# drive_board.net
KiCad netlist of a schematic drawn in EAGLE
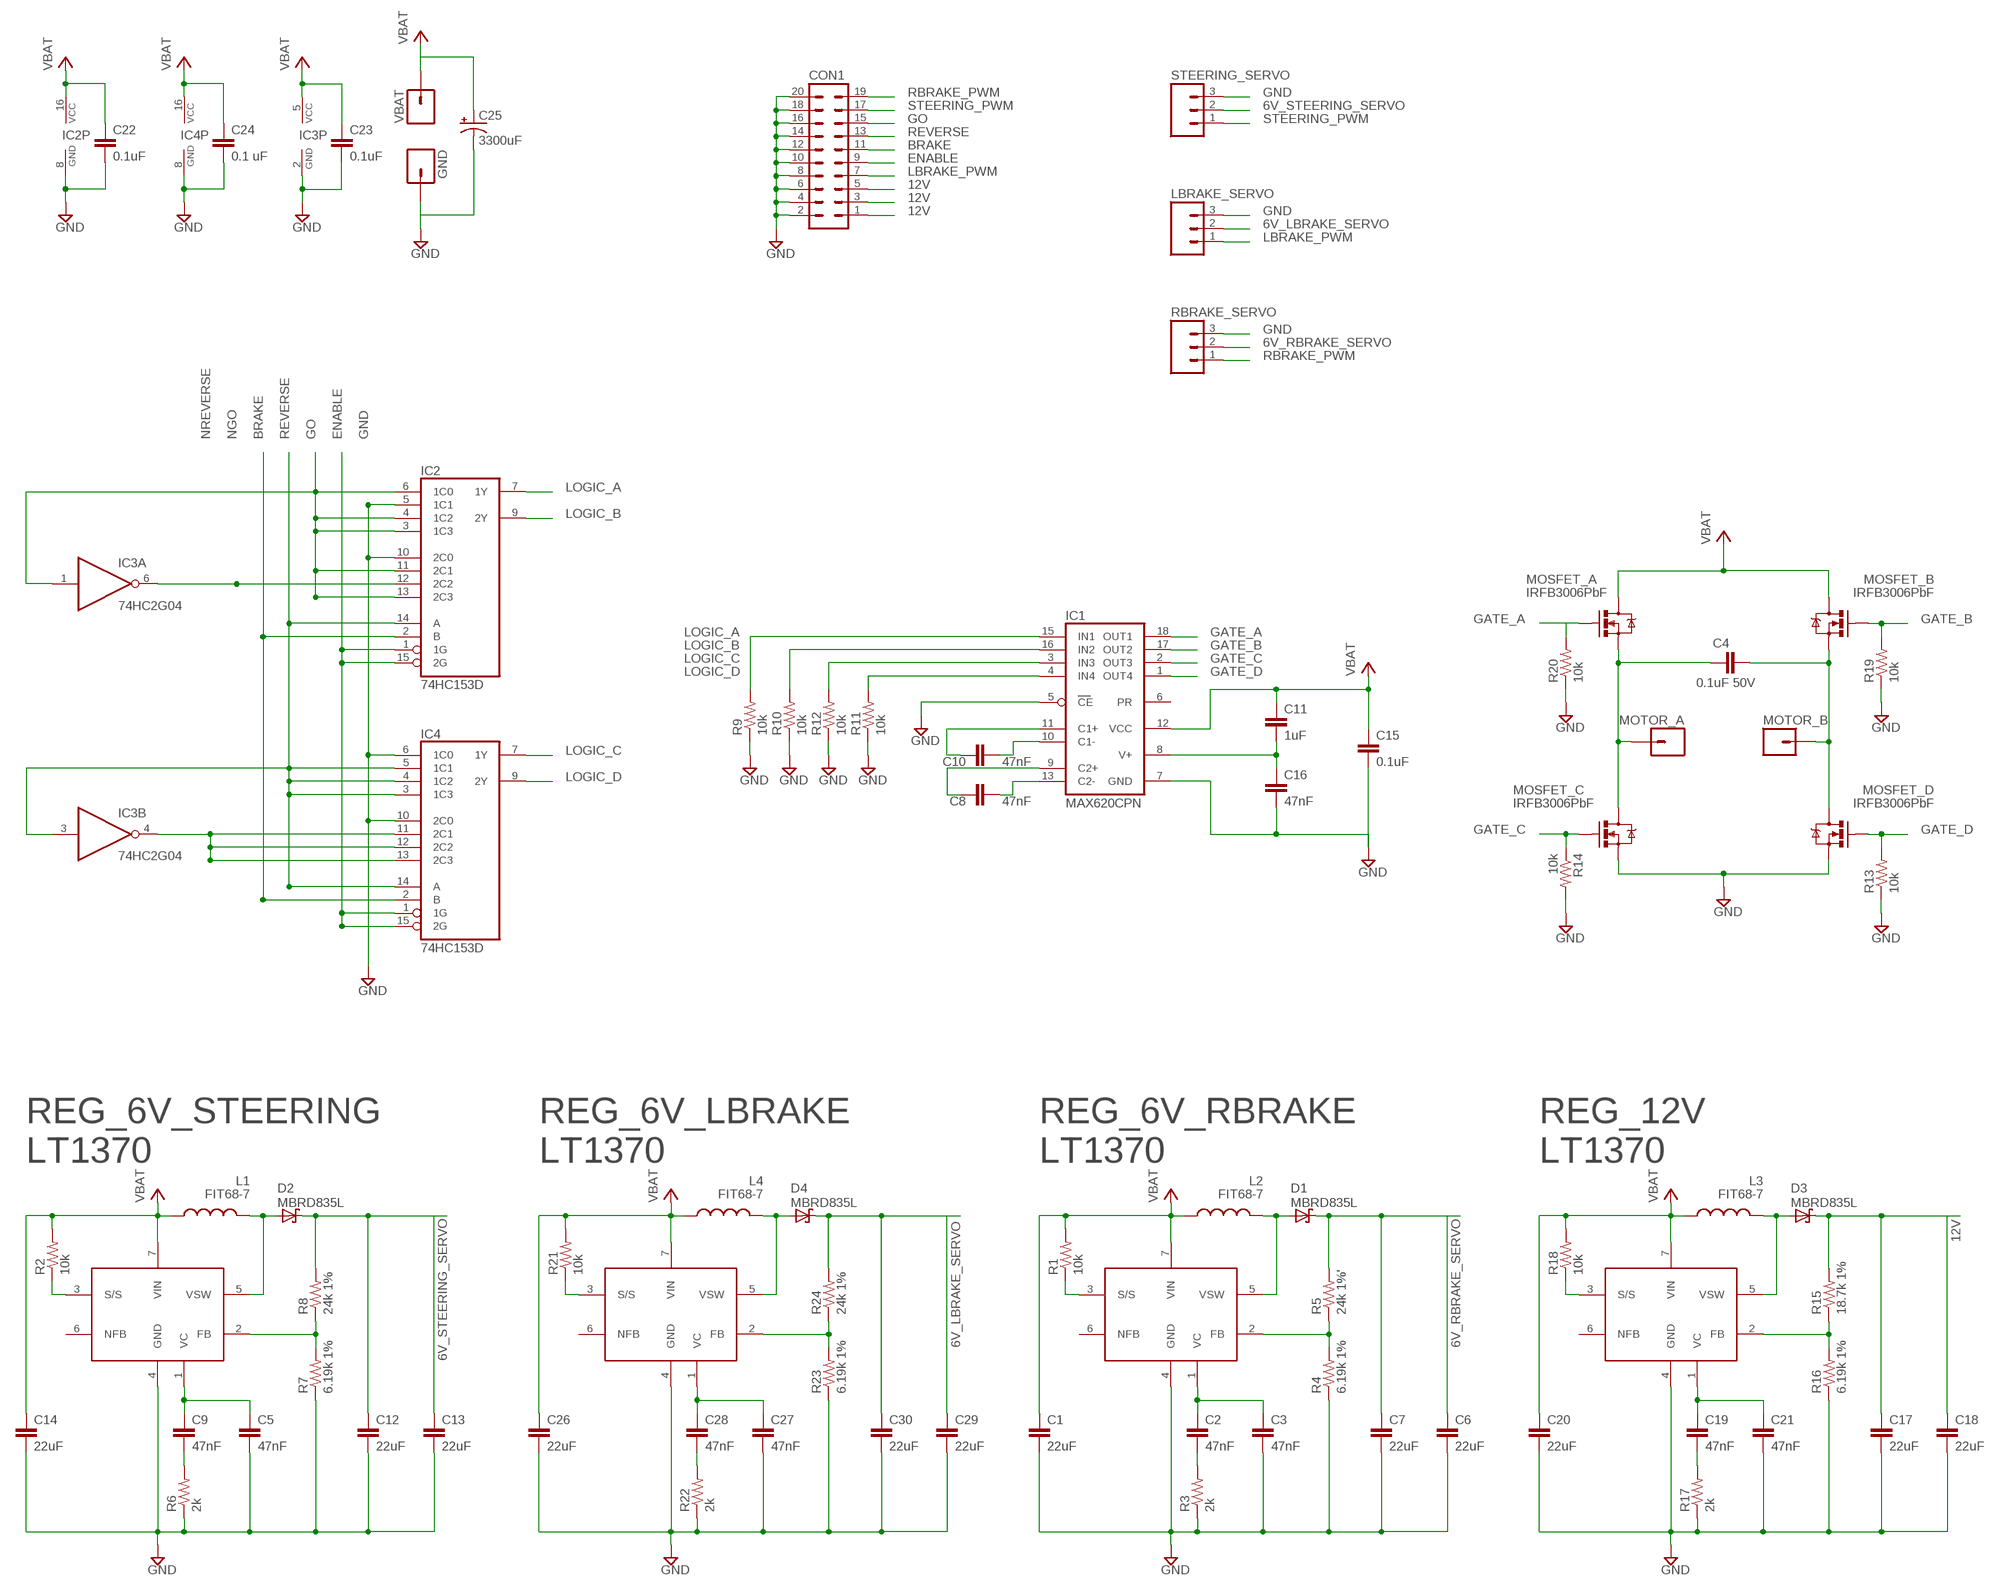
[diagram p0: schematic, sheet 1]

(export (version "E")
  (design (tool "Eeschema 10.0.6"))
  (components
    (comp (ref "C1")
      (value "22uF")
      (footprint "eagle-import:CAPACITOR_CASE_D")
      (libsource (lib "eagle-import") (part "TPSD226M025R0200"))
    )
    (comp (ref "C2")
      (value "47nF")
      (footprint "eagle-import:0603-CAP")
      (libsource (lib "eagle-import") (part "CAP0603-CAP"))
    )
    (comp (ref "C3")
      (value "47nF")
      (footprint "eagle-import:0603-CAP")
      (libsource (lib "eagle-import") (part "CAP0603-CAP"))
    )
    (comp (ref "C4")
      (value "0.1uF 50V")
      (footprint "eagle-import:0603-CAP")
      (libsource (lib "eagle-import") (part "CAP0603-CAP"))
    )
    (comp (ref "C5")
      (value "47nF")
      (footprint "eagle-import:0603-CAP")
      (libsource (lib "eagle-import") (part "CAP0603-CAP"))
    )
    (comp (ref "C6")
      (value "22uF")
      (footprint "eagle-import:CAPACITOR_CASE_D")
      (libsource (lib "eagle-import") (part "TPSD226M025R0200"))
    )
    (comp (ref "C7")
      (value "22uF")
      (footprint "eagle-import:CAPACITOR_CASE_D")
      (libsource (lib "eagle-import") (part "TPSD226M025R0200"))
    )
    (comp (ref "C8")
      (value "47nF")
      (footprint "eagle-import:0603-CAP")
      (libsource (lib "eagle-import") (part "CAP0603-CAP"))
    )
    (comp (ref "C9")
      (value "47nF")
      (footprint "eagle-import:0603-CAP")
      (libsource (lib "eagle-import") (part "CAP0603-CAP"))
    )
    (comp (ref "C10")
      (value "47nF")
      (footprint "eagle-import:0603-CAP")
      (libsource (lib "eagle-import") (part "CAP0603-CAP"))
    )
    (comp (ref "C11")
      (value "1uF")
      (footprint "eagle-import:0603-CAP")
      (libsource (lib "eagle-import") (part "CAP0603-CAP"))
    )
    (comp (ref "C12")
      (value "22uF")
      (footprint "eagle-import:CAPACITOR_CASE_D")
      (libsource (lib "eagle-import") (part "TPSD226M025R0200"))
    )
    (comp (ref "C13")
      (value "22uF")
      (footprint "eagle-import:CAPACITOR_CASE_D")
      (libsource (lib "eagle-import") (part "TPSD226M025R0200"))
    )
    (comp (ref "C14")
      (value "22uF")
      (footprint "eagle-import:CAPACITOR_CASE_D")
      (libsource (lib "eagle-import") (part "TPSD226M025R0200"))
    )
    (comp (ref "C15")
      (value "0.1uF")
      (footprint "eagle-import:0603-CAP")
      (libsource (lib "eagle-import") (part "CAP0603-CAP"))
    )
    (comp (ref "C16")
      (value "47nF")
      (footprint "eagle-import:0603-CAP")
      (libsource (lib "eagle-import") (part "CAP0603-CAP"))
    )
    (comp (ref "C17")
      (value "22uF")
      (footprint "eagle-import:CAPACITOR_CASE_D")
      (libsource (lib "eagle-import") (part "TPSD226M025R0200"))
    )
    (comp (ref "C18")
      (value "22uF")
      (footprint "eagle-import:CAPACITOR_CASE_D")
      (libsource (lib "eagle-import") (part "TPSD226M025R0200"))
    )
    (comp (ref "C19")
      (value "47nF")
      (footprint "eagle-import:0603-CAP")
      (libsource (lib "eagle-import") (part "CAP0603-CAP"))
    )
    (comp (ref "C20")
      (value "22uF")
      (footprint "eagle-import:CAPACITOR_CASE_D")
      (libsource (lib "eagle-import") (part "TPSD226M025R0200"))
    )
    (comp (ref "C21")
      (value "47nF")
      (footprint "eagle-import:0603-CAP")
      (libsource (lib "eagle-import") (part "CAP0603-CAP"))
    )
    (comp (ref "C22")
      (value "0.1uF")
      (footprint "eagle-import:0603-CAP")
      (libsource (lib "eagle-import") (part "SparkFun-Passives_CAP0603-CAP"))
    )
    (comp (ref "C23")
      (value "0.1uF")
      (footprint "eagle-import:0603-CAP")
      (libsource (lib "eagle-import") (part "SparkFun-Passives_CAP0603-CAP"))
    )
    (comp (ref "C24")
      (value "0.1 uF")
      (footprint "eagle-import:0603-CAP")
      (libsource (lib "eagle-import") (part "SparkFun-Passives_CAP0603-CAP"))
    )
    (comp (ref "C25")
      (value "3300uF")
      (footprint "eagle-import:CPOL-RADIAL-100UF-25V")
      (libsource (lib "eagle-import") (part "CAP_POLPTH1"))
    )
    (comp (ref "C26")
      (value "22uF")
      (footprint "eagle-import:CAPACITOR_CASE_D")
      (libsource (lib "eagle-import") (part "TPSD226M025R0200"))
    )
    (comp (ref "C27")
      (value "47nF")
      (footprint "eagle-import:0603-CAP")
      (libsource (lib "eagle-import") (part "CAP0603-CAP"))
    )
    (comp (ref "C28")
      (value "47nF")
      (footprint "eagle-import:0603-CAP")
      (libsource (lib "eagle-import") (part "CAP0603-CAP"))
    )
    (comp (ref "C29")
      (value "22uF")
      (footprint "eagle-import:CAPACITOR_CASE_D")
      (libsource (lib "eagle-import") (part "TPSD226M025R0200"))
    )
    (comp (ref "C30")
      (value "22uF")
      (footprint "eagle-import:CAPACITOR_CASE_D")
      (libsource (lib "eagle-import") (part "TPSD226M025R0200"))
    )
    (comp (ref "CON1")
      (value "ML20")
      (footprint "eagle-import:ML20")
      (libsource (lib "eagle-import") (part "ML20"))
    )
    (comp (ref "D1")
      (value "MBRD835L")
      (footprint "eagle-import:DPACK_1")
      (libsource (lib "eagle-import") (part "MBRD835L"))
    )
    (comp (ref "D2")
      (value "MBRD835L")
      (footprint "eagle-import:DPACK_1")
      (libsource (lib "eagle-import") (part "MBRD835L"))
    )
    (comp (ref "D3")
      (value "MBRD835L")
      (footprint "eagle-import:DPACK_1")
      (libsource (lib "eagle-import") (part "MBRD835L"))
    )
    (comp (ref "D4")
      (value "MBRD835L")
      (footprint "eagle-import:DPACK_1")
      (libsource (lib "eagle-import") (part "MBRD835L"))
    )
    (comp (ref "GND")
      (value "GND")
      (footprint "eagle-import:PAD_12GA")
      (libsource (lib "eagle-import") (part "PAD_12GAPTH"))
    )
    (comp (ref "IC1")
      (value "MAX620CPN")
      (footprint "eagle-import:DIL18")
      (fields (field (name "MPN") "MAX620CPN+"))
      (libsource (lib "eagle-import") (part "MAX620CPN"))
    )
    (comp (ref "IC2")
      (value "74HC153D")
      (footprint "eagle-import:SO16")
      (libsource (lib "eagle-import") (part "74153DHC"))
    )
    (comp (ref "IC3")
      (value "74HC2G04")
      (footprint "eagle-import:TSSOP6")
      (libsource (lib "eagle-import") (part "74HC2G04"))
    )
    (comp (ref "IC4")
      (value "74HC153D")
      (footprint "eagle-import:SO16")
      (libsource (lib "eagle-import") (part "74153DHC"))
    )
    (comp (ref "L1")
      (value "FIT68-7")
      (footprint "eagle-import:TOROID_INDUCTOR")
      (libsource (lib "eagle-import") (part "INDUCTOR"))
    )
    (comp (ref "L2")
      (value "FIT68-7")
      (footprint "eagle-import:TOROID_INDUCTOR")
      (libsource (lib "eagle-import") (part "INDUCTOR"))
    )
    (comp (ref "L3")
      (value "FIT68-7")
      (footprint "eagle-import:TOROID_INDUCTOR")
      (libsource (lib "eagle-import") (part "INDUCTOR"))
    )
    (comp (ref "L4")
      (value "FIT68-7")
      (footprint "eagle-import:TOROID_INDUCTOR")
      (libsource (lib "eagle-import") (part "INDUCTOR"))
    )
    (comp (ref "LBRAKE_SERVO")
      (value "M03POLAR")
      (footprint "eagle-import:MOLEX-1X3")
      (libsource (lib "eagle-import") (part "M03POLAR"))
    )
    (comp (ref "MOSFET_A")
      (value "IRFB3006PbF")
      (footprint "eagle-import:TO220V")
      (libsource (lib "eagle-import") (part "MOSFET-NCHANNELPTH2"))
    )
    (comp (ref "MOSFET_B")
      (value "IRFB3006PbF")
      (footprint "eagle-import:TO220V")
      (libsource (lib "eagle-import") (part "MOSFET-NCHANNELPTH2"))
    )
    (comp (ref "MOSFET_C")
      (value "IRFB3006PbF")
      (footprint "eagle-import:TO220V")
      (libsource (lib "eagle-import") (part "MOSFET-NCHANNELPTH2"))
    )
    (comp (ref "MOSFET_D")
      (value "IRFB3006PbF")
      (footprint "eagle-import:TO220V")
      (libsource (lib "eagle-import") (part "MOSFET-NCHANNELPTH2"))
    )
    (comp (ref "MOTOR_A")
      (value "MOTOR A")
      (footprint "eagle-import:PAD_12GA")
      (libsource (lib "eagle-import") (part "PAD_12GAPTH"))
    )
    (comp (ref "MOTOR_B")
      (value "MOTOR B")
      (footprint "eagle-import:PAD_12GA")
      (libsource (lib "eagle-import") (part "PAD_12GAPTH"))
    )
    (comp (ref "R1")
      (value "10k")
      (footprint "eagle-import:0603-RES")
      (libsource (lib "eagle-import") (part "RESISTOR0603-RES"))
    )
    (comp (ref "R2")
      (value "10k")
      (footprint "eagle-import:0603-RES")
      (libsource (lib "eagle-import") (part "RESISTOR0603-RES"))
    )
    (comp (ref "R3")
      (value "2k")
      (footprint "eagle-import:0603-RES")
      (libsource (lib "eagle-import") (part "RESISTOR0603-RES"))
    )
    (comp (ref "R4")
      (value "6.19k 1%")
      (footprint "eagle-import:0603-RES")
      (libsource (lib "eagle-import") (part "RESISTOR0603-RES"))
    )
    (comp (ref "R5")
      (value "24k 1%'")
      (footprint "eagle-import:0603-RES")
      (libsource (lib "eagle-import") (part "RESISTOR0603-RES"))
    )
    (comp (ref "R6")
      (value "2k")
      (footprint "eagle-import:0603-RES")
      (libsource (lib "eagle-import") (part "RESISTOR0603-RES"))
    )
    (comp (ref "R7")
      (value "6.19k 1%")
      (footprint "eagle-import:0603-RES")
      (libsource (lib "eagle-import") (part "RESISTOR0603-RES"))
    )
    (comp (ref "R8")
      (value "24k 1%")
      (footprint "eagle-import:0603-RES")
      (libsource (lib "eagle-import") (part "RESISTOR0603-RES"))
    )
    (comp (ref "R9")
      (value "10k")
      (footprint "eagle-import:0603-RES")
      (libsource (lib "eagle-import") (part "RESISTOR0603-RES"))
    )
    (comp (ref "R10")
      (value "10k")
      (footprint "eagle-import:0603-RES")
      (libsource (lib "eagle-import") (part "RESISTOR0603-RES"))
    )
    (comp (ref "R11")
      (value "10k")
      (footprint "eagle-import:0603-RES")
      (libsource (lib "eagle-import") (part "RESISTOR0603-RES"))
    )
    (comp (ref "R12")
      (value "10k")
      (footprint "eagle-import:0603-RES")
      (libsource (lib "eagle-import") (part "RESISTOR0603-RES"))
    )
    (comp (ref "R13")
      (value "10k")
      (footprint "eagle-import:0603-RES")
      (libsource (lib "eagle-import") (part "RESISTOR0603-RES"))
    )
    (comp (ref "R14")
      (value "10k")
      (footprint "eagle-import:0603-RES")
      (libsource (lib "eagle-import") (part "RESISTOR0603-RES"))
    )
    (comp (ref "R15")
      (value "18.7k 1%")
      (footprint "eagle-import:0603-RES")
      (libsource (lib "eagle-import") (part "RESISTOR0603-RES"))
    )
    (comp (ref "R16")
      (value "6.19k 1%")
      (footprint "eagle-import:0603-RES")
      (libsource (lib "eagle-import") (part "RESISTOR0603-RES"))
    )
    (comp (ref "R17")
      (value "2k")
      (footprint "eagle-import:0603-RES")
      (libsource (lib "eagle-import") (part "RESISTOR0603-RES"))
    )
    (comp (ref "R18")
      (value "10k")
      (footprint "eagle-import:0603-RES")
      (libsource (lib "eagle-import") (part "RESISTOR0603-RES"))
    )
    (comp (ref "R19")
      (value "10k")
      (footprint "eagle-import:0603-RES")
      (libsource (lib "eagle-import") (part "RESISTOR0603-RES"))
    )
    (comp (ref "R20")
      (value "10k")
      (footprint "eagle-import:0603-RES")
      (libsource (lib "eagle-import") (part "RESISTOR0603-RES"))
    )
    (comp (ref "R21")
      (value "10k")
      (footprint "eagle-import:0603-RES")
      (libsource (lib "eagle-import") (part "RESISTOR0603-RES"))
    )
    (comp (ref "R22")
      (value "2k")
      (footprint "eagle-import:0603-RES")
      (libsource (lib "eagle-import") (part "RESISTOR0603-RES"))
    )
    (comp (ref "R23")
      (value "6.19k 1%")
      (footprint "eagle-import:0603-RES")
      (libsource (lib "eagle-import") (part "RESISTOR0603-RES"))
    )
    (comp (ref "R24")
      (value "24k 1%")
      (footprint "eagle-import:0603-RES")
      (libsource (lib "eagle-import") (part "RESISTOR0603-RES"))
    )
    (comp (ref "RBRAKE_SERVO")
      (value "M03POLAR")
      (footprint "eagle-import:MOLEX-1X3")
      (libsource (lib "eagle-import") (part "M03POLAR"))
    )
    (comp (ref "REG_6V_LBRAKE")
      (value "LT1370")
      (footprint "eagle-import:TO220-7")
      (libsource (lib "eagle-import") (part "LT1370"))
    )
    (comp (ref "REG_6V_RBRAKE")
      (value "LT1370")
      (footprint "eagle-import:TO220-7")
      (libsource (lib "eagle-import") (part "LT1370"))
    )
    (comp (ref "REG_6V_STEERING")
      (value "LT1370")
      (footprint "eagle-import:TO220-7")
      (libsource (lib "eagle-import") (part "LT1370"))
    )
    (comp (ref "REG_12V")
      (value "LT1370")
      (footprint "eagle-import:TO220-7")
      (libsource (lib "eagle-import") (part "LT1370"))
    )
    (comp (ref "STEERING_SERVO")
      (value "M03POLAR")
      (footprint "eagle-import:MOLEX-1X3")
      (libsource (lib "eagle-import") (part "M03POLAR"))
    )
    (comp (ref "VBAT")
      (value "7.2V")
      (footprint "eagle-import:PAD_12GA")
      (libsource (lib "eagle-import") (part "PAD_12GAPTH"))
    )
  )
  (nets
    (net (code "1") (name "/6V_LBRAKE_SERVO") (class "Default")
      (node (ref "C29") (pin "P$1") (pinfunction "1_P$1") (pintype "passive"))
      (node (ref "C30") (pin "P$1") (pinfunction "1_P$1") (pintype "passive"))
      (node (ref "D4") (pin "C") (pinfunction "C_C") (pintype "passive"))
      (node (ref "LBRAKE_SERVO") (pin "2") (pinfunction "2_2") (pintype "passive"))
      (node (ref "R24") (pin "2") (pinfunction "2_2") (pintype "passive"))
    )
    (net (code "2") (name "/6V_RBRAKE_SERVO") (class "Default")
      (node (ref "C6") (pin "P$1") (pinfunction "1_P$1") (pintype "passive"))
      (node (ref "C7") (pin "P$1") (pinfunction "1_P$1") (pintype "passive"))
      (node (ref "D1") (pin "C") (pinfunction "C_C") (pintype "passive"))
      (node (ref "R5") (pin "2") (pinfunction "2_2") (pintype "passive"))
      (node (ref "RBRAKE_SERVO") (pin "2") (pinfunction "2_2") (pintype "passive"))
    )
    (net (code "3") (name "/6V_STEERING_SERVO") (class "Default")
      (node (ref "C12") (pin "P$1") (pinfunction "1_P$1") (pintype "passive"))
      (node (ref "C13") (pin "P$1") (pinfunction "1_P$1") (pintype "passive"))
      (node (ref "D2") (pin "C") (pinfunction "C_C") (pintype "passive"))
      (node (ref "R8") (pin "2") (pinfunction "2_2") (pintype "passive"))
      (node (ref "STEERING_SERVO") (pin "2") (pinfunction "2_2") (pintype "passive"))
    )
    (net (code "4") (name "/12V") (class "Default")
      (node (ref "C17") (pin "P$1") (pinfunction "1_P$1") (pintype "passive"))
      (node (ref "C18") (pin "P$1") (pinfunction "1_P$1") (pintype "passive"))
      (node (ref "CON1") (pin "1") (pinfunction "1_1") (pintype "passive"))
      (node (ref "CON1") (pin "3") (pinfunction "3_3") (pintype "passive"))
      (node (ref "CON1") (pin "5") (pinfunction "5_5") (pintype "passive"))
      (node (ref "D3") (pin "C") (pinfunction "C_C") (pintype "passive"))
      (node (ref "R15") (pin "2") (pinfunction "2_2") (pintype "passive"))
    )
    (net (code "5") (name "/BRAKE") (class "Default")
      (node (ref "CON1") (pin "11") (pinfunction "11_11") (pintype "passive"))
      (node (ref "IC2") (pin "2") (pinfunction "B_2") (pintype "input"))
      (node (ref "IC4") (pin "2") (pinfunction "B_2") (pintype "input"))
    )
    (net (code "6") (name "/ENABLE") (class "Default")
      (node (ref "CON1") (pin "9") (pinfunction "9_9") (pintype "passive"))
      (node (ref "IC2") (pin "1") (pinfunction "1G_1") (pintype "input"))
      (node (ref "IC2") (pin "15") (pinfunction "2G_15") (pintype "input"))
      (node (ref "IC4") (pin "1") (pinfunction "1G_1") (pintype "input"))
      (node (ref "IC4") (pin "15") (pinfunction "2G_15") (pintype "input"))
    )
    (net (code "7") (name "/GATE_A") (class "Default")
      (node (ref "IC1") (pin "18") (pinfunction "OUT1_18") (pintype "output"))
      (node (ref "MOSFET_A") (pin "1") (pinfunction "G_1") (pintype "passive"))
      (node (ref "R20") (pin "2") (pinfunction "2_2") (pintype "passive"))
    )
    (net (code "8") (name "/GATE_B") (class "Default")
      (node (ref "IC1") (pin "17") (pinfunction "OUT2_17") (pintype "output"))
      (node (ref "MOSFET_B") (pin "1") (pinfunction "G_1") (pintype "passive"))
      (node (ref "R19") (pin "2") (pinfunction "2_2") (pintype "passive"))
    )
    (net (code "9") (name "/GATE_C") (class "Default")
      (node (ref "IC1") (pin "2") (pinfunction "OUT3_2") (pintype "output"))
      (node (ref "MOSFET_C") (pin "1") (pinfunction "G_1") (pintype "passive"))
      (node (ref "R14") (pin "1") (pinfunction "1_1") (pintype "passive"))
    )
    (net (code "10") (name "/GATE_D") (class "Default")
      (node (ref "IC1") (pin "1") (pinfunction "OUT4_1") (pintype "output"))
      (node (ref "MOSFET_D") (pin "1") (pinfunction "G_1") (pintype "passive"))
      (node (ref "R13") (pin "2") (pinfunction "2_2") (pintype "passive"))
    )
    (net (code "11") (name "/GO") (class "Default")
      (node (ref "CON1") (pin "15") (pinfunction "15_15") (pintype "passive"))
      (node (ref "IC2") (pin "11") (pinfunction "2C1_11") (pintype "input"))
      (node (ref "IC2") (pin "13") (pinfunction "2C3_13") (pintype "input"))
      (node (ref "IC2") (pin "3") (pinfunction "1C3_3") (pintype "input"))
      (node (ref "IC2") (pin "4") (pinfunction "1C2_4") (pintype "input"))
      (node (ref "IC2") (pin "6") (pinfunction "1C0_6") (pintype "input"))
      (node (ref "IC3") (pin "1") (pinfunction "I_1") (pintype "input"))
    )
    (net (code "12") (name "/LBRAKE_PWM") (class "Default")
      (node (ref "CON1") (pin "7") (pinfunction "7_7") (pintype "passive"))
      (node (ref "LBRAKE_SERVO") (pin "1") (pinfunction "1_1") (pintype "passive"))
    )
    (net (code "13") (name "/LOGIC_A") (class "Default")
      (node (ref "IC1") (pin "15") (pinfunction "IN1_15") (pintype "input"))
      (node (ref "IC2") (pin "7") (pinfunction "1Y_7") (pintype "output"))
      (node (ref "R9") (pin "2") (pinfunction "2_2") (pintype "passive"))
    )
    (net (code "14") (name "/LOGIC_B") (class "Default")
      (node (ref "IC1") (pin "16") (pinfunction "IN2_16") (pintype "input"))
      (node (ref "IC2") (pin "9") (pinfunction "2Y_9") (pintype "output"))
      (node (ref "R10") (pin "2") (pinfunction "2_2") (pintype "passive"))
    )
    (net (code "15") (name "/LOGIC_C") (class "Default")
      (node (ref "IC1") (pin "3") (pinfunction "IN3_3") (pintype "input"))
      (node (ref "IC4") (pin "7") (pinfunction "1Y_7") (pintype "output"))
      (node (ref "R12") (pin "2") (pinfunction "2_2") (pintype "passive"))
    )
    (net (code "16") (name "/LOGIC_D") (class "Default")
      (node (ref "IC1") (pin "4") (pinfunction "IN4_4") (pintype "input"))
      (node (ref "IC4") (pin "9") (pinfunction "2Y_9") (pintype "output"))
      (node (ref "R11") (pin "2") (pinfunction "2_2") (pintype "passive"))
    )
    (net (code "17") (name "/NGO") (class "Default")
      (node (ref "IC2") (pin "12") (pinfunction "2C2_12") (pintype "input"))
      (node (ref "IC3") (pin "6") (pinfunction "O_6") (pintype "output"))
    )
    (net (code "18") (name "/NREVERSE") (class "Default")
      (node (ref "IC3") (pin "4") (pinfunction "O_4") (pintype "output"))
      (node (ref "IC4") (pin "11") (pinfunction "2C1_11") (pintype "input"))
      (node (ref "IC4") (pin "12") (pinfunction "2C2_12") (pintype "input"))
      (node (ref "IC4") (pin "13") (pinfunction "2C3_13") (pintype "input"))
    )
    (net (code "19") (name "/RBRAKE_PWM") (class "Default")
      (node (ref "CON1") (pin "19") (pinfunction "19_19") (pintype "passive"))
      (node (ref "RBRAKE_SERVO") (pin "1") (pinfunction "1_1") (pintype "passive"))
    )
    (net (code "20") (name "/REVERSE") (class "Default")
      (node (ref "CON1") (pin "13") (pinfunction "13_13") (pintype "passive"))
      (node (ref "IC2") (pin "14") (pinfunction "A_14") (pintype "input"))
      (node (ref "IC3") (pin "3") (pinfunction "I_3") (pintype "input"))
      (node (ref "IC4") (pin "14") (pinfunction "A_14") (pintype "input"))
      (node (ref "IC4") (pin "3") (pinfunction "1C3_3") (pintype "input"))
      (node (ref "IC4") (pin "4") (pinfunction "1C2_4") (pintype "input"))
      (node (ref "IC4") (pin "5") (pinfunction "1C1_5") (pintype "input"))
    )
    (net (code "21") (name "/STEERING_PWM") (class "Default")
      (node (ref "CON1") (pin "17") (pinfunction "17_17") (pintype "passive"))
      (node (ref "STEERING_SERVO") (pin "1") (pinfunction "1_1") (pintype "passive"))
    )
    (net (code "22") (name "GND") (class "Default")
      (node (ref "C1") (pin "P$2") (pinfunction "2_P$2") (pintype "passive"))
      (node (ref "C12") (pin "P$2") (pinfunction "2_P$2") (pintype "passive"))
      (node (ref "C13") (pin "P$2") (pinfunction "2_P$2") (pintype "passive"))
      (node (ref "C14") (pin "P$2") (pinfunction "2_P$2") (pintype "passive"))
      (node (ref "C15") (pin "2") (pinfunction "2_2") (pintype "passive"))
      (node (ref "C16") (pin "2") (pinfunction "2_2") (pintype "passive"))
      (node (ref "C17") (pin "P$2") (pinfunction "2_P$2") (pintype "passive"))
      (node (ref "C18") (pin "P$2") (pinfunction "2_P$2") (pintype "passive"))
      (node (ref "C20") (pin "P$2") (pinfunction "2_P$2") (pintype "passive"))
      (node (ref "C21") (pin "2") (pinfunction "2_2") (pintype "passive"))
      (node (ref "C22") (pin "2") (pinfunction "2_2") (pintype "passive"))
      (node (ref "C23") (pin "2") (pinfunction "2_2") (pintype "passive"))
      (node (ref "C24") (pin "2") (pinfunction "2_2") (pintype "passive"))
      (node (ref "C25") (pin "2") (pinfunction "-_2") (pintype "passive"))
      (node (ref "C26") (pin "P$2") (pinfunction "2_P$2") (pintype "passive"))
      (node (ref "C27") (pin "2") (pinfunction "2_2") (pintype "passive"))
      (node (ref "C29") (pin "P$2") (pinfunction "2_P$2") (pintype "passive"))
      (node (ref "C3") (pin "2") (pinfunction "2_2") (pintype "passive"))
      (node (ref "C30") (pin "P$2") (pinfunction "2_P$2") (pintype "passive"))
      (node (ref "C5") (pin "2") (pinfunction "2_2") (pintype "passive"))
      (node (ref "C6") (pin "P$2") (pinfunction "2_P$2") (pintype "passive"))
      (node (ref "C7") (pin "P$2") (pinfunction "2_P$2") (pintype "passive"))
      (node (ref "CON1") (pin "10") (pinfunction "10_10") (pintype "passive"))
      (node (ref "CON1") (pin "12") (pinfunction "12_12") (pintype "passive"))
      (node (ref "CON1") (pin "14") (pinfunction "14_14") (pintype "passive"))
      (node (ref "CON1") (pin "16") (pinfunction "16_16") (pintype "passive"))
      (node (ref "CON1") (pin "18") (pinfunction "18_18") (pintype "passive"))
      (node (ref "CON1") (pin "2") (pinfunction "2_2") (pintype "passive"))
      (node (ref "CON1") (pin "20") (pinfunction "20_20") (pintype "passive"))
      (node (ref "CON1") (pin "4") (pinfunction "4_4") (pintype "passive"))
      (node (ref "CON1") (pin "6") (pinfunction "6_6") (pintype "passive"))
      (node (ref "CON1") (pin "8") (pinfunction "8_8") (pintype "passive"))
      (node (ref "GND") (pin "1") (pinfunction "1_1") (pintype "passive"))
      (node (ref "IC1") (pin "5") (pinfunction "CE_5") (pintype "input"))
      (node (ref "IC1") (pin "7") (pinfunction "GND_7") (pintype "power_in"))
      (node (ref "IC2") (pin "10") (pinfunction "2C0_10") (pintype "input"))
      (node (ref "IC2") (pin "5") (pinfunction "1C1_5") (pintype "input"))
      (node (ref "IC2") (pin "8") (pinfunction "GND_8") (pintype "power_in"))
      (node (ref "IC3") (pin "2") (pinfunction "GND_2") (pintype "power_in"))
      (node (ref "IC4") (pin "10") (pinfunction "2C0_10") (pintype "input"))
      (node (ref "IC4") (pin "6") (pinfunction "1C0_6") (pintype "input"))
      (node (ref "IC4") (pin "8") (pinfunction "GND_8") (pintype "power_in"))
      (node (ref "LBRAKE_SERVO") (pin "3") (pinfunction "3_3") (pintype "passive"))
      (node (ref "MOSFET_C") (pin "3") (pinfunction "S_3") (pintype "passive"))
      (node (ref "MOSFET_D") (pin "3") (pinfunction "S_3") (pintype "passive"))
      (node (ref "R10") (pin "1") (pinfunction "1_1") (pintype "passive"))
      (node (ref "R11") (pin "1") (pinfunction "1_1") (pintype "passive"))
      (node (ref "R12") (pin "1") (pinfunction "1_1") (pintype "passive"))
      (node (ref "R13") (pin "1") (pinfunction "1_1") (pintype "passive"))
      (node (ref "R14") (pin "2") (pinfunction "2_2") (pintype "passive"))
      (node (ref "R16") (pin "1") (pinfunction "1_1") (pintype "passive"))
      (node (ref "R17") (pin "1") (pinfunction "1_1") (pintype "passive"))
      (node (ref "R19") (pin "1") (pinfunction "1_1") (pintype "passive"))
      (node (ref "R20") (pin "1") (pinfunction "1_1") (pintype "passive"))
      (node (ref "R22") (pin "1") (pinfunction "1_1") (pintype "passive"))
      (node (ref "R23") (pin "1") (pinfunction "1_1") (pintype "passive"))
      (node (ref "R3") (pin "1") (pinfunction "1_1") (pintype "passive"))
      (node (ref "R4") (pin "1") (pinfunction "1_1") (pintype "passive"))
      (node (ref "R6") (pin "1") (pinfunction "1_1") (pintype "passive"))
      (node (ref "R7") (pin "1") (pinfunction "1_1") (pintype "passive"))
      (node (ref "R9") (pin "1") (pinfunction "1_1") (pintype "passive"))
      (node (ref "RBRAKE_SERVO") (pin "3") (pinfunction "3_3") (pintype "passive"))
      (node (ref "REG_12V") (pin "4") (pinfunction "GND_4") (pintype "bidirectional"))
      (node (ref "REG_6V_LBRAKE") (pin "4") (pinfunction "GND_4") (pintype "bidirectional"))
      (node (ref "REG_6V_RBRAKE") (pin "4") (pinfunction "GND_4") (pintype "bidirectional"))
      (node (ref "REG_6V_STEERING") (pin "4") (pinfunction "GND_4") (pintype "bidirectional"))
      (node (ref "STEERING_SERVO") (pin "3") (pinfunction "3_3") (pintype "passive"))
    )
    (net (code "23") (name "Net-(C2-Pad2)") (class "Default")
      (node (ref "C2") (pin "2") (pinfunction "2_2") (pintype "passive"))
      (node (ref "R3") (pin "2") (pinfunction "2_2") (pintype "passive"))
    )
    (net (code "24") (name "Net-(C9-Pad2)") (class "Default")
      (node (ref "C9") (pin "2") (pinfunction "2_2") (pintype "passive"))
      (node (ref "R6") (pin "2") (pinfunction "2_2") (pintype "passive"))
    )
    (net (code "25") (name "Net-(C19-Pad2)") (class "Default")
      (node (ref "C19") (pin "2") (pinfunction "2_2") (pintype "passive"))
      (node (ref "R17") (pin "2") (pinfunction "2_2") (pintype "passive"))
    )
    (net (code "26") (name "Net-(C28-Pad2)") (class "Default")
      (node (ref "C28") (pin "2") (pinfunction "2_2") (pintype "passive"))
      (node (ref "R22") (pin "2") (pinfunction "2_2") (pintype "passive"))
    )
    (net (code "27") (name "Net-(IC1-C1+)") (class "Default")
      (node (ref "C10") (pin "1") (pinfunction "1_1") (pintype "passive"))
      (node (ref "IC1") (pin "11") (pinfunction "C1+_11") (pintype "passive"))
    )
    (net (code "28") (name "Net-(IC1-C1-)") (class "Default")
      (node (ref "C10") (pin "2") (pinfunction "2_2") (pintype "passive"))
      (node (ref "IC1") (pin "10") (pinfunction "C1-_10") (pintype "passive"))
    )
    (net (code "29") (name "Net-(IC1-C2+)") (class "Default")
      (node (ref "C8") (pin "1") (pinfunction "1_1") (pintype "passive"))
      (node (ref "IC1") (pin "9") (pinfunction "C2+_9") (pintype "passive"))
    )
    (net (code "30") (name "Net-(IC1-C2-)") (class "Default")
      (node (ref "C8") (pin "2") (pinfunction "2_2") (pintype "passive"))
      (node (ref "IC1") (pin "13") (pinfunction "C2-_13") (pintype "passive"))
    )
    (net (code "31") (name "Net-(IC1-V+)") (class "Default")
      (node (ref "C11") (pin "2") (pinfunction "2_2") (pintype "passive"))
      (node (ref "C16") (pin "1") (pinfunction "1_1") (pintype "passive"))
      (node (ref "IC1") (pin "8") (pinfunction "V+_8") (pintype "power_in"))
    )
    (net (code "32") (name "Net-(MOSFET_A-S)") (class "Default")
      (node (ref "C4") (pin "1") (pinfunction "1_1") (pintype "passive"))
      (node (ref "MOSFET_A") (pin "3") (pinfunction "S_3") (pintype "passive"))
      (node (ref "MOSFET_C") (pin "2") (pinfunction "D_2") (pintype "passive"))
      (node (ref "MOTOR_A") (pin "1") (pinfunction "1_1") (pintype "passive"))
    )
    (net (code "33") (name "Net-(MOSFET_B-S)") (class "Default")
      (node (ref "C4") (pin "2") (pinfunction "2_2") (pintype "passive"))
      (node (ref "MOSFET_B") (pin "3") (pinfunction "S_3") (pintype "passive"))
      (node (ref "MOSFET_D") (pin "2") (pinfunction "D_2") (pintype "passive"))
      (node (ref "MOTOR_B") (pin "1") (pinfunction "1_1") (pintype "passive"))
    )
    (net (code "34") (name "Net-(REG_6V_LBRAKE-FB)") (class "Default")
      (node (ref "R23") (pin "2") (pinfunction "2_2") (pintype "passive"))
      (node (ref "R24") (pin "1") (pinfunction "1_1") (pintype "passive"))
      (node (ref "REG_6V_LBRAKE") (pin "2") (pinfunction "FB_2") (pintype "bidirectional"))
    )
    (net (code "35") (name "Net-(REG_6V_LBRAKE-S{slash}S)") (class "Default")
      (node (ref "R21") (pin "1") (pinfunction "1_1") (pintype "passive"))
      (node (ref "REG_6V_LBRAKE") (pin "3") (pinfunction "S/S_3") (pintype "bidirectional"))
    )
    (net (code "36") (name "Net-(REG_6V_LBRAKE-VC)") (class "Default")
      (node (ref "C27") (pin "1") (pinfunction "1_1") (pintype "passive"))
      (node (ref "C28") (pin "1") (pinfunction "1_1") (pintype "passive"))
      (node (ref "REG_6V_LBRAKE") (pin "1") (pinfunction "VC_1") (pintype "bidirectional"))
    )
    (net (code "37") (name "Net-(REG_6V_LBRAKE-VSW)") (class "Default")
      (node (ref "D4") (pin "B") (pinfunction "A_B") (pintype "passive"))
      (node (ref "D4") (pin "E") (pinfunction "A_E") (pintype "passive"))
      (node (ref "L4") (pin "2") (pinfunction "2_2") (pintype "passive"))
      (node (ref "REG_6V_LBRAKE") (pin "5") (pinfunction "VSW_5") (pintype "bidirectional"))
    )
    (net (code "38") (name "Net-(REG_6V_RBRAKE-FB)") (class "Default")
      (node (ref "R4") (pin "2") (pinfunction "2_2") (pintype "passive"))
      (node (ref "R5") (pin "1") (pinfunction "1_1") (pintype "passive"))
      (node (ref "REG_6V_RBRAKE") (pin "2") (pinfunction "FB_2") (pintype "bidirectional"))
    )
    (net (code "39") (name "Net-(REG_6V_RBRAKE-S{slash}S)") (class "Default")
      (node (ref "R1") (pin "1") (pinfunction "1_1") (pintype "passive"))
      (node (ref "REG_6V_RBRAKE") (pin "3") (pinfunction "S/S_3") (pintype "bidirectional"))
    )
    (net (code "40") (name "Net-(REG_6V_RBRAKE-VC)") (class "Default")
      (node (ref "C2") (pin "1") (pinfunction "1_1") (pintype "passive"))
      (node (ref "C3") (pin "1") (pinfunction "1_1") (pintype "passive"))
      (node (ref "REG_6V_RBRAKE") (pin "1") (pinfunction "VC_1") (pintype "bidirectional"))
    )
    (net (code "41") (name "Net-(REG_6V_RBRAKE-VSW)") (class "Default")
      (node (ref "D1") (pin "B") (pinfunction "A_B") (pintype "passive"))
      (node (ref "D1") (pin "E") (pinfunction "A_E") (pintype "passive"))
      (node (ref "L2") (pin "2") (pinfunction "2_2") (pintype "passive"))
      (node (ref "REG_6V_RBRAKE") (pin "5") (pinfunction "VSW_5") (pintype "bidirectional"))
    )
    (net (code "42") (name "Net-(REG_6V_STEERING-FB)") (class "Default")
      (node (ref "R7") (pin "2") (pinfunction "2_2") (pintype "passive"))
      (node (ref "R8") (pin "1") (pinfunction "1_1") (pintype "passive"))
      (node (ref "REG_6V_STEERING") (pin "2") (pinfunction "FB_2") (pintype "bidirectional"))
    )
    (net (code "43") (name "Net-(REG_6V_STEERING-S{slash}S)") (class "Default")
      (node (ref "R2") (pin "1") (pinfunction "1_1") (pintype "passive"))
      (node (ref "REG_6V_STEERING") (pin "3") (pinfunction "S/S_3") (pintype "bidirectional"))
    )
    (net (code "44") (name "Net-(REG_6V_STEERING-VC)") (class "Default")
      (node (ref "C5") (pin "1") (pinfunction "1_1") (pintype "passive"))
      (node (ref "C9") (pin "1") (pinfunction "1_1") (pintype "passive"))
      (node (ref "REG_6V_STEERING") (pin "1") (pinfunction "VC_1") (pintype "bidirectional"))
    )
    (net (code "45") (name "Net-(REG_6V_STEERING-VSW)") (class "Default")
      (node (ref "D2") (pin "B") (pinfunction "A_B") (pintype "passive"))
      (node (ref "D2") (pin "E") (pinfunction "A_E") (pintype "passive"))
      (node (ref "L1") (pin "2") (pinfunction "2_2") (pintype "passive"))
      (node (ref "REG_6V_STEERING") (pin "5") (pinfunction "VSW_5") (pintype "bidirectional"))
    )
    (net (code "46") (name "Net-(REG_12V-FB)") (class "Default")
      (node (ref "R15") (pin "1") (pinfunction "1_1") (pintype "passive"))
      (node (ref "R16") (pin "2") (pinfunction "2_2") (pintype "passive"))
      (node (ref "REG_12V") (pin "2") (pinfunction "FB_2") (pintype "bidirectional"))
    )
    (net (code "47") (name "Net-(REG_12V-S{slash}S)") (class "Default")
      (node (ref "R18") (pin "1") (pinfunction "1_1") (pintype "passive"))
      (node (ref "REG_12V") (pin "3") (pinfunction "S/S_3") (pintype "bidirectional"))
    )
    (net (code "48") (name "Net-(REG_12V-VC)") (class "Default")
      (node (ref "C19") (pin "1") (pinfunction "1_1") (pintype "passive"))
      (node (ref "C21") (pin "1") (pinfunction "1_1") (pintype "passive"))
      (node (ref "REG_12V") (pin "1") (pinfunction "VC_1") (pintype "bidirectional"))
    )
    (net (code "49") (name "Net-(REG_12V-VSW)") (class "Default")
      (node (ref "D3") (pin "B") (pinfunction "A_B") (pintype "passive"))
      (node (ref "D3") (pin "E") (pinfunction "A_E") (pintype "passive"))
      (node (ref "L3") (pin "2") (pinfunction "2_2") (pintype "passive"))
      (node (ref "REG_12V") (pin "5") (pinfunction "VSW_5") (pintype "bidirectional"))
    )
    (net (code "50") (name "VBAT") (class "Default")
      (node (ref "C1") (pin "P$1") (pinfunction "1_P$1") (pintype "passive"))
      (node (ref "C11") (pin "1") (pinfunction "1_1") (pintype "passive"))
      (node (ref "C14") (pin "P$1") (pinfunction "1_P$1") (pintype "passive"))
      (node (ref "C15") (pin "1") (pinfunction "1_1") (pintype "passive"))
      (node (ref "C20") (pin "P$1") (pinfunction "1_P$1") (pintype "passive"))
      (node (ref "C22") (pin "1") (pinfunction "1_1") (pintype "passive"))
      (node (ref "C23") (pin "1") (pinfunction "1_1") (pintype "passive"))
      (node (ref "C24") (pin "1") (pinfunction "1_1") (pintype "passive"))
      (node (ref "C25") (pin "1") (pinfunction "+_1") (pintype "passive"))
      (node (ref "C26") (pin "P$1") (pinfunction "1_P$1") (pintype "passive"))
      (node (ref "IC1") (pin "12") (pinfunction "VCC_12") (pintype "power_in"))
      (node (ref "IC2") (pin "16") (pinfunction "VCC_16") (pintype "power_in"))
      (node (ref "IC3") (pin "5") (pinfunction "VCC_5") (pintype "power_in"))
      (node (ref "IC4") (pin "16") (pinfunction "VCC_16") (pintype "power_in"))
      (node (ref "L1") (pin "1") (pinfunction "1_1") (pintype "passive"))
      (node (ref "L2") (pin "1") (pinfunction "1_1") (pintype "passive"))
      (node (ref "L3") (pin "1") (pinfunction "1_1") (pintype "passive"))
      (node (ref "L4") (pin "1") (pinfunction "1_1") (pintype "passive"))
      (node (ref "MOSFET_A") (pin "2") (pinfunction "D_2") (pintype "passive"))
      (node (ref "MOSFET_B") (pin "2") (pinfunction "D_2") (pintype "passive"))
      (node (ref "R1") (pin "2") (pinfunction "2_2") (pintype "passive"))
      (node (ref "R18") (pin "2") (pinfunction "2_2") (pintype "passive"))
      (node (ref "R2") (pin "2") (pinfunction "2_2") (pintype "passive"))
      (node (ref "R21") (pin "2") (pinfunction "2_2") (pintype "passive"))
      (node (ref "REG_12V") (pin "7") (pinfunction "VIN_7") (pintype "bidirectional"))
      (node (ref "REG_6V_LBRAKE") (pin "7") (pinfunction "VIN_7") (pintype "bidirectional"))
      (node (ref "REG_6V_RBRAKE") (pin "7") (pinfunction "VIN_7") (pintype "bidirectional"))
      (node (ref "REG_6V_STEERING") (pin "7") (pinfunction "VIN_7") (pintype "bidirectional"))
      (node (ref "VBAT") (pin "1") (pinfunction "1_1") (pintype "passive"))
    )
    (net (code "51") (name "unconnected-(IC1-PR-Pad6)") (class "Default")
      (node (ref "IC1") (pin "6") (pinfunction "PR_6") (pintype "output"))
    )
    (net (code "52") (name "unconnected-(REG_6V_LBRAKE-NFB-Pad6)") (class "Default")
      (node (ref "REG_6V_LBRAKE") (pin "6") (pinfunction "NFB_6") (pintype "bidirectional"))
    )
    (net (code "53") (name "unconnected-(REG_6V_RBRAKE-NFB-Pad6)") (class "Default")
      (node (ref "REG_6V_RBRAKE") (pin "6") (pinfunction "NFB_6") (pintype "bidirectional"))
    )
    (net (code "54") (name "unconnected-(REG_6V_STEERING-NFB-Pad6)") (class "Default")
      (node (ref "REG_6V_STEERING") (pin "6") (pinfunction "NFB_6") (pintype "bidirectional"))
    )
    (net (code "55") (name "unconnected-(REG_12V-NFB-Pad6)") (class "Default")
      (node (ref "REG_12V") (pin "6") (pinfunction "NFB_6") (pintype "bidirectional"))
    )
  )
)
